# Power_Part_V1_0.net
KiCad netlist of a schematic drawn in Altium Designer
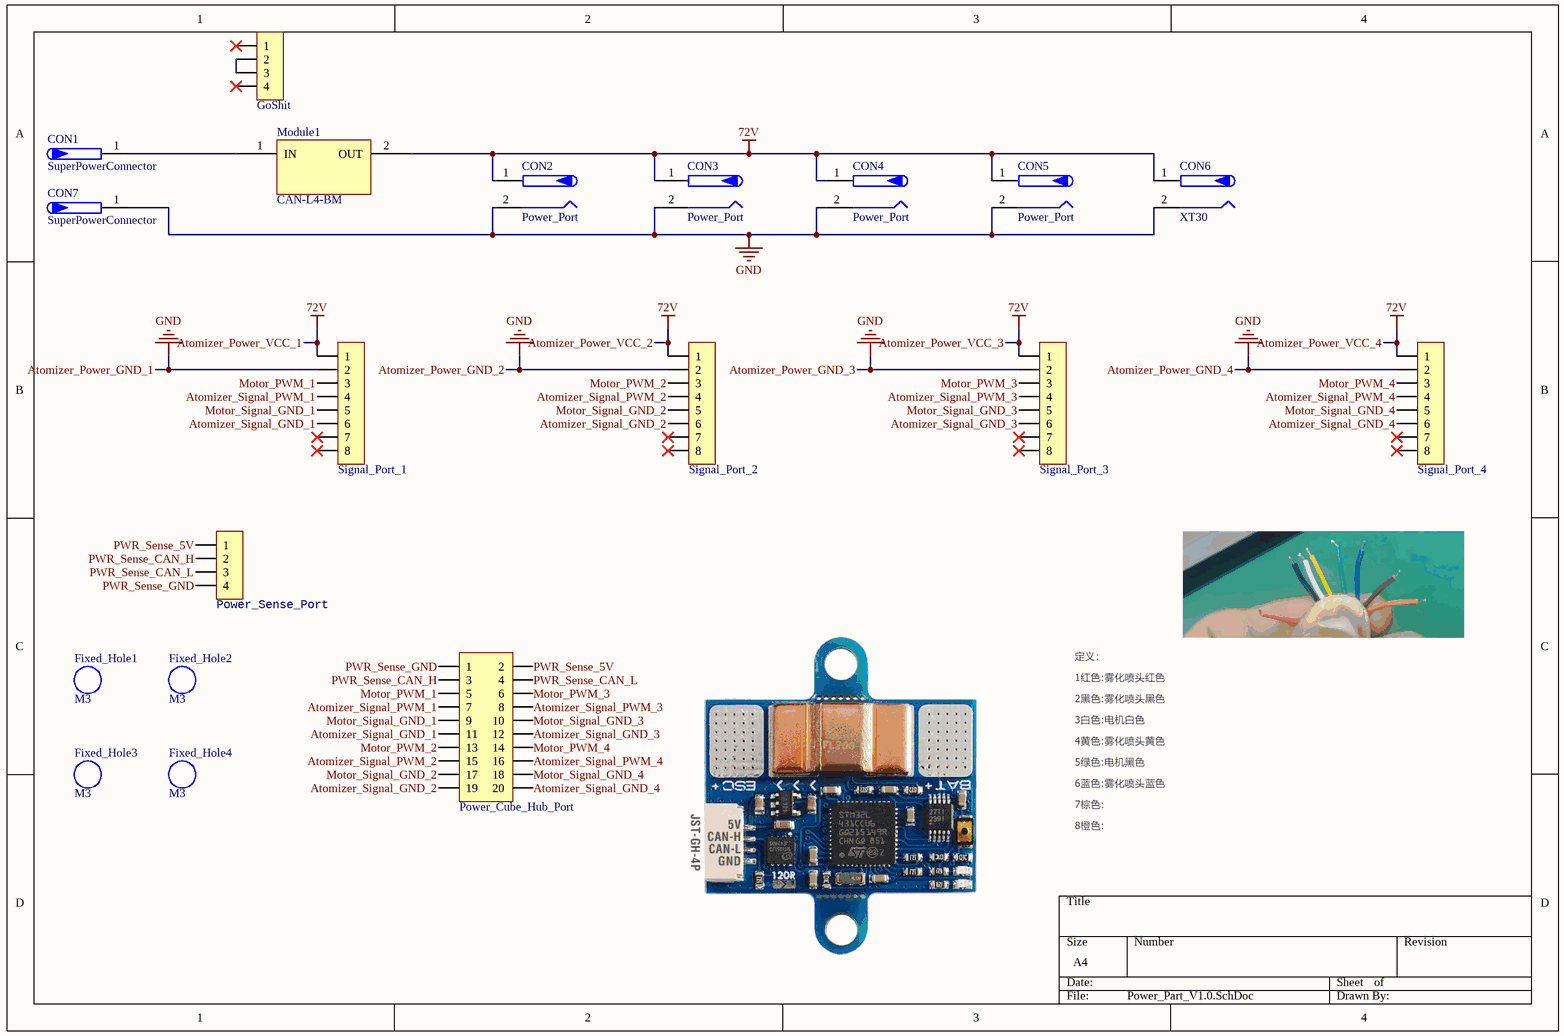
[diagram p0: Power_Part_V1.0.SchDoc]

(export (version "E")
  (design (tool "Eeschema 10.0.6"))
  (components
    (comp (ref "CON1")
      (value "SuperPowerConnector")
      (footprint "SuperPowerConnector")
      (libsource (lib "Schlib2") (part "SuperPowerConnector"))
    )
    (comp (ref "CON2")
      (value "Power_Port")
      (footprint "PAD1")
      (description "电源接口")
      (libsource (lib "4.1   - 接口类") (part "XT电源接口-2Pins"))
    )
    (comp (ref "CON3")
      (value "Power_Port")
      (footprint "PAD1")
      (description "电源接口")
      (libsource (lib "4.1   - 接口类") (part "XT电源接口-2Pins"))
    )
    (comp (ref "CON4")
      (value "Power_Port")
      (footprint "PAD1")
      (description "电源接口")
      (libsource (lib "4.1   - 接口类") (part "XT电源接口-2Pins"))
    )
    (comp (ref "CON5")
      (value "Power_Port")
      (footprint "PAD1")
      (description "电源接口")
      (libsource (lib "4.1   - 接口类") (part "XT电源接口-2Pins"))
    )
    (comp (ref "CON6")
      (value "XT30")
      (footprint "XT30U-F")
      (description "电源接口")
      (libsource (lib "4.1   - 接口类") (part "XT电源接口-2Pins"))
    )
    (comp (ref "CON7")
      (value "SuperPowerConnector")
      (footprint "SuperPowerConnector")
      (libsource (lib "Schlib2") (part "SuperPowerConnector"))
    )
    (comp (ref "Fixed_Hole1")
      (value "M3")
      (footprint "M3 140X350")
      (description "铜柱孔")
      (libsource (lib "15.1 - 调试、辅助器件") (part "M3"))
    )
    (comp (ref "Fixed_Hole2")
      (value "M3")
      (footprint "M3 140X350")
      (description "铜柱孔")
      (libsource (lib "15.1 - 调试、辅助器件") (part "M3"))
    )
    (comp (ref "Fixed_Hole3")
      (value "M3")
      (footprint "M3 140X350")
      (description "铜柱孔")
      (libsource (lib "15.1 - 调试、辅助器件") (part "M3"))
    )
    (comp (ref "Fixed_Hole4")
      (value "M3")
      (footprint "M3 140X350")
      (description "铜柱孔")
      (libsource (lib "15.1 - 调试、辅助器件") (part "M3"))
    )
    (comp (ref "GoShit")
      (value "HDR-1X4")
      (footprint "KF128-3.81-4P")
      (description "4P接插件")
      (libsource (lib "4.8   - 接插件-脚距3.81") (part "Header 4"))
    )
    (comp (ref "Module1")
      (value "CAN-L4-BM")
      (footprint "CAN-L4-BM")
      (libsource (lib "Schlib2") (part "CAN-L4-BM"))
    )
    (comp (ref "Power_Cube_Hub_Port")
      (value "Header 2X10")
      (footprint "IDC2.54-LI-2x10P")
      (description "10*2P接插件")
      (libsource (lib "4.6   - 接插件-脚距2.54") (part "Header 10X2"))
    )
    (comp (ref "Power_Sense_Port")
      (value "HDR-1X4")
      (footprint "GH1.25-WS-4P")
      (description "4P接插件")
      (libsource (lib "17.1  -GH1.25") (part "Header 4"))
    )
    (comp (ref "Signal_Port_1")
      (value "HDR-1X8")
      (footprint "HDR2.54-LI-8P")
      (description "8P接插件")
      (libsource (lib "4.6   - 接插件-脚距2.54") (part "Header 8"))
    )
    (comp (ref "Signal_Port_2")
      (value "HDR-1X8")
      (footprint "HDR2.54-LI-8P")
      (description "8P接插件")
      (libsource (lib "4.6   - 接插件-脚距2.54") (part "Header 8"))
    )
    (comp (ref "Signal_Port_3")
      (value "HDR-1X8")
      (footprint "HDR2.54-LI-8P")
      (description "8P接插件")
      (libsource (lib "4.6   - 接插件-脚距2.54") (part "Header 8"))
    )
    (comp (ref "Signal_Port_4")
      (value "HDR-1X8")
      (footprint "HDR2.54-LI-8P")
      (description "8P接插件")
      (libsource (lib "4.6   - 接插件-脚距2.54") (part "Header 8"))
    )
  )
  (nets
    (net (code "1") (name "/Atomizer_Signal_GND_1") (class "Default")
      (node (ref "Power_Cube_Hub_Port") (pin "11") (pinfunction "11_11") (pintype "passive"))
      (node (ref "Signal_Port_1") (pin "6") (pinfunction "6_6") (pintype "passive"))
    )
    (net (code "2") (name "/Atomizer_Signal_GND_2") (class "Default")
      (node (ref "Power_Cube_Hub_Port") (pin "19") (pinfunction "19_19") (pintype "passive"))
      (node (ref "Signal_Port_2") (pin "6") (pinfunction "6_6") (pintype "passive"))
    )
    (net (code "3") (name "/Atomizer_Signal_GND_3") (class "Default")
      (node (ref "Power_Cube_Hub_Port") (pin "12") (pinfunction "12_12") (pintype "passive"))
      (node (ref "Signal_Port_3") (pin "6") (pinfunction "6_6") (pintype "passive"))
    )
    (net (code "4") (name "/Atomizer_Signal_GND_4") (class "Default")
      (node (ref "Power_Cube_Hub_Port") (pin "20") (pinfunction "20_20") (pintype "passive"))
      (node (ref "Signal_Port_4") (pin "6") (pinfunction "6_6") (pintype "passive"))
    )
    (net (code "5") (name "/Atomizer_Signal_PWM_1") (class "Default")
      (node (ref "Power_Cube_Hub_Port") (pin "7") (pinfunction "7_7") (pintype "passive"))
      (node (ref "Signal_Port_1") (pin "4") (pinfunction "4_4") (pintype "passive"))
    )
    (net (code "6") (name "/Atomizer_Signal_PWM_2") (class "Default")
      (node (ref "Power_Cube_Hub_Port") (pin "15") (pinfunction "15_15") (pintype "passive"))
      (node (ref "Signal_Port_2") (pin "4") (pinfunction "4_4") (pintype "passive"))
    )
    (net (code "7") (name "/Atomizer_Signal_PWM_3") (class "Default")
      (node (ref "Power_Cube_Hub_Port") (pin "8") (pinfunction "8_8") (pintype "passive"))
      (node (ref "Signal_Port_3") (pin "4") (pinfunction "4_4") (pintype "passive"))
    )
    (net (code "8") (name "/Atomizer_Signal_PWM_4") (class "Default")
      (node (ref "Power_Cube_Hub_Port") (pin "16") (pinfunction "16_16") (pintype "passive"))
      (node (ref "Signal_Port_4") (pin "4") (pinfunction "4_4") (pintype "passive"))
    )
    (net (code "9") (name "/Motor_PWM_1") (class "Default")
      (node (ref "Power_Cube_Hub_Port") (pin "5") (pinfunction "5_5") (pintype "passive"))
      (node (ref "Signal_Port_1") (pin "3") (pinfunction "3_3") (pintype "passive"))
    )
    (net (code "10") (name "/Motor_PWM_2") (class "Default")
      (node (ref "Power_Cube_Hub_Port") (pin "13") (pinfunction "13_13") (pintype "passive"))
      (node (ref "Signal_Port_2") (pin "3") (pinfunction "3_3") (pintype "passive"))
    )
    (net (code "11") (name "/Motor_PWM_3") (class "Default")
      (node (ref "Power_Cube_Hub_Port") (pin "6") (pinfunction "6_6") (pintype "passive"))
      (node (ref "Signal_Port_3") (pin "3") (pinfunction "3_3") (pintype "passive"))
    )
    (net (code "12") (name "/Motor_PWM_4") (class "Default")
      (node (ref "Power_Cube_Hub_Port") (pin "14") (pinfunction "14_14") (pintype "passive"))
      (node (ref "Signal_Port_4") (pin "3") (pinfunction "3_3") (pintype "passive"))
    )
    (net (code "13") (name "/Motor_Signal_GND_1") (class "Default")
      (node (ref "Power_Cube_Hub_Port") (pin "9") (pinfunction "9_9") (pintype "passive"))
      (node (ref "Signal_Port_1") (pin "5") (pinfunction "5_5") (pintype "passive"))
    )
    (net (code "14") (name "/Motor_Signal_GND_2") (class "Default")
      (node (ref "Power_Cube_Hub_Port") (pin "17") (pinfunction "17_17") (pintype "passive"))
      (node (ref "Signal_Port_2") (pin "5") (pinfunction "5_5") (pintype "passive"))
    )
    (net (code "15") (name "/Motor_Signal_GND_3") (class "Default")
      (node (ref "Power_Cube_Hub_Port") (pin "10") (pinfunction "10_10") (pintype "passive"))
      (node (ref "Signal_Port_3") (pin "5") (pinfunction "5_5") (pintype "passive"))
    )
    (net (code "16") (name "/Motor_Signal_GND_4") (class "Default")
      (node (ref "Power_Cube_Hub_Port") (pin "18") (pinfunction "18_18") (pintype "passive"))
      (node (ref "Signal_Port_4") (pin "5") (pinfunction "5_5") (pintype "passive"))
    )
    (net (code "17") (name "/PWR_Sense_5V") (class "Default")
      (node (ref "Power_Cube_Hub_Port") (pin "2") (pinfunction "2_2") (pintype "passive"))
      (node (ref "Power_Sense_Port") (pin "1") (pinfunction "1_1") (pintype "passive"))
    )
    (net (code "18") (name "/PWR_Sense_CAN_H") (class "Default")
      (node (ref "Power_Cube_Hub_Port") (pin "3") (pinfunction "3_3") (pintype "passive"))
      (node (ref "Power_Sense_Port") (pin "2") (pinfunction "2_2") (pintype "passive"))
    )
    (net (code "19") (name "/PWR_Sense_CAN_L") (class "Default")
      (node (ref "Power_Cube_Hub_Port") (pin "4") (pinfunction "4_4") (pintype "passive"))
      (node (ref "Power_Sense_Port") (pin "3") (pinfunction "3_3") (pintype "passive"))
    )
    (net (code "20") (name "/PWR_Sense_GND") (class "Default")
      (node (ref "Power_Cube_Hub_Port") (pin "1") (pinfunction "1_1") (pintype "passive"))
      (node (ref "Power_Sense_Port") (pin "4") (pinfunction "4_4") (pintype "passive"))
    )
    (net (code "21") (name "72V") (class "Default")
      (node (ref "CON2") (pin "1") (pintype "power_in"))
      (node (ref "CON3") (pin "1") (pintype "power_in"))
      (node (ref "CON4") (pin "1") (pintype "power_in"))
      (node (ref "CON5") (pin "1") (pintype "power_in"))
      (node (ref "CON6") (pin "1") (pintype "power_in"))
      (node (ref "Module1") (pin "2") (pinfunction "OUT_2") (pintype "passive"))
      (node (ref "Signal_Port_1") (pin "1") (pinfunction "1_1") (pintype "passive"))
      (node (ref "Signal_Port_2") (pin "1") (pinfunction "1_1") (pintype "passive"))
      (node (ref "Signal_Port_3") (pin "1") (pinfunction "1_1") (pintype "passive"))
      (node (ref "Signal_Port_4") (pin "1") (pinfunction "1_1") (pintype "passive"))
    )
    (net (code "22") (name "GND") (class "Default")
      (node (ref "CON2") (pin "2") (pintype "power_in"))
      (node (ref "CON3") (pin "2") (pintype "power_in"))
      (node (ref "CON4") (pin "2") (pintype "power_in"))
      (node (ref "CON5") (pin "2") (pintype "power_in"))
      (node (ref "CON6") (pin "2") (pintype "power_in"))
      (node (ref "CON7") (pin "1") (pintype "power_in"))
      (node (ref "Signal_Port_1") (pin "2") (pinfunction "2_2") (pintype "passive"))
      (node (ref "Signal_Port_2") (pin "2") (pinfunction "2_2") (pintype "passive"))
      (node (ref "Signal_Port_3") (pin "2") (pinfunction "2_2") (pintype "passive"))
      (node (ref "Signal_Port_4") (pin "2") (pinfunction "2_2") (pintype "passive"))
    )
    (net (code "23") (name "Net-(GoShit-Pad2)") (class "Default")
      (node (ref "GoShit") (pin "2") (pinfunction "2_2") (pintype "passive"))
      (node (ref "GoShit") (pin "3") (pinfunction "3_3") (pintype "passive"))
    )
    (net (code "24") (name "Net-(Module1-IN)") (class "Default")
      (node (ref "CON1") (pin "1") (pintype "power_in"))
      (node (ref "Module1") (pin "1") (pinfunction "IN_1") (pintype "passive"))
    )
    (net (code "25") (name "unconnected-(GoShit-Pad1)") (class "Default")
      (node (ref "GoShit") (pin "1") (pinfunction "1_1") (pintype "passive+no_connect"))
    )
    (net (code "26") (name "unconnected-(GoShit-Pad4)") (class "Default")
      (node (ref "GoShit") (pin "4") (pinfunction "4_4") (pintype "passive+no_connect"))
    )
    (net (code "27") (name "unconnected-(Signal_Port_1-Pad7)") (class "Default")
      (node (ref "Signal_Port_1") (pin "7") (pinfunction "7_7") (pintype "passive+no_connect"))
    )
    (net (code "28") (name "unconnected-(Signal_Port_1-Pad8)") (class "Default")
      (node (ref "Signal_Port_1") (pin "8") (pinfunction "8_8") (pintype "passive+no_connect"))
    )
    (net (code "29") (name "unconnected-(Signal_Port_2-Pad7)") (class "Default")
      (node (ref "Signal_Port_2") (pin "7") (pinfunction "7_7") (pintype "passive+no_connect"))
    )
    (net (code "30") (name "unconnected-(Signal_Port_2-Pad8)") (class "Default")
      (node (ref "Signal_Port_2") (pin "8") (pinfunction "8_8") (pintype "passive+no_connect"))
    )
    (net (code "31") (name "unconnected-(Signal_Port_3-Pad7)") (class "Default")
      (node (ref "Signal_Port_3") (pin "7") (pinfunction "7_7") (pintype "passive+no_connect"))
    )
    (net (code "32") (name "unconnected-(Signal_Port_3-Pad8)") (class "Default")
      (node (ref "Signal_Port_3") (pin "8") (pinfunction "8_8") (pintype "passive+no_connect"))
    )
    (net (code "33") (name "unconnected-(Signal_Port_4-Pad7)") (class "Default")
      (node (ref "Signal_Port_4") (pin "7") (pinfunction "7_7") (pintype "passive+no_connect"))
    )
    (net (code "34") (name "unconnected-(Signal_Port_4-Pad8)") (class "Default")
      (node (ref "Signal_Port_4") (pin "8") (pinfunction "8_8") (pintype "passive+no_connect"))
    )
  )
)
